# EEG-Electrodes.net
KiCad netlist of a schematic drawn in Altium Designer
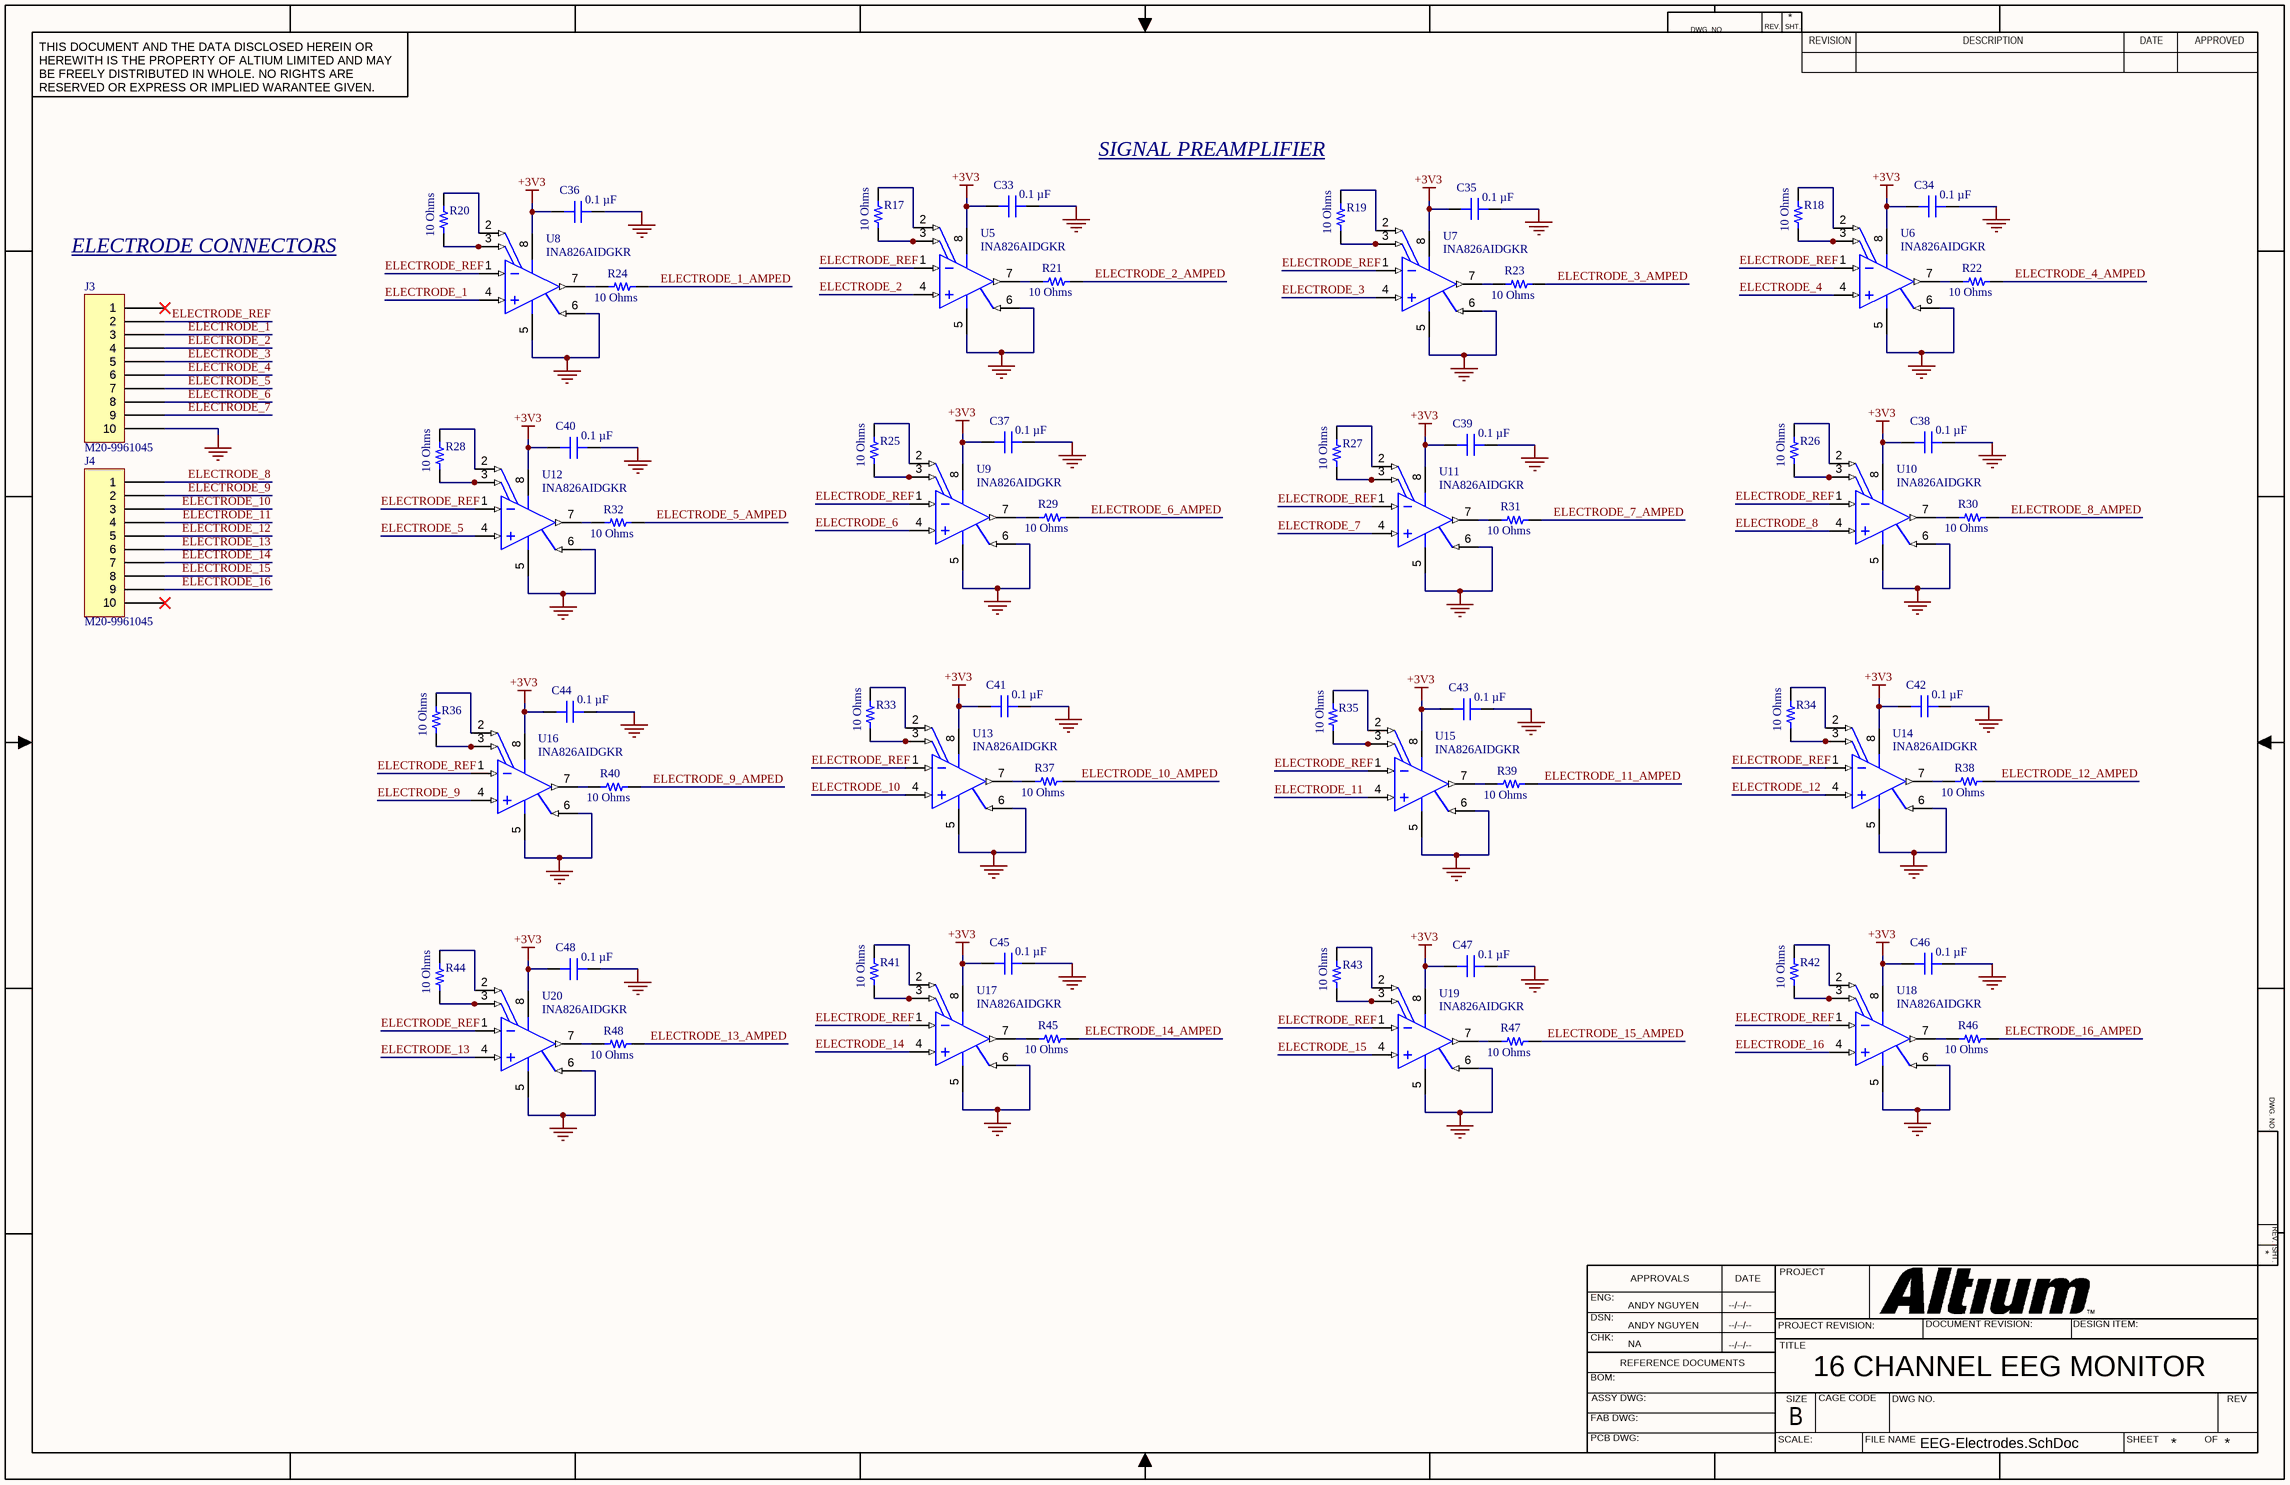
[diagram p0: EEG-Electrodes.SchDoc]

(export (version "E")
  (design (tool "Eeschema 10.0.6"))
  (components
    (comp (ref "C33")
      (value "0.1 µF")
      (footprint "CAP 0402_1005")
      (description "CAP CER 0402 0.1UF 16V X7R 10%")
      (fields (field (name "PART NUMBER") "C0402C104K4RECAUTO") (field (name "MANUFACTURER") "KEMET"))
      (libsource (lib "Celestial Altium Library - altium_library") (part "Capacitor"))
    )
    (comp (ref "C34")
      (value "0.1 µF")
      (footprint "CAP 0402_1005")
      (description "CAP CER 0402 0.1UF 16V X7R 10%")
      (fields (field (name "PART NUMBER") "C0402C104K4RECAUTO") (field (name "MANUFACTURER") "KEMET"))
      (libsource (lib "Celestial Altium Library - altium_library") (part "Capacitor"))
    )
    (comp (ref "C35")
      (value "0.1 µF")
      (footprint "CAP 0402_1005")
      (description "CAP CER 0402 0.1UF 16V X7R 10%")
      (fields (field (name "PART NUMBER") "C0402C104K4RECAUTO") (field (name "MANUFACTURER") "KEMET"))
      (libsource (lib "Celestial Altium Library - altium_library") (part "Capacitor"))
    )
    (comp (ref "C36")
      (value "0.1 µF")
      (footprint "CAP 0402_1005")
      (description "CAP CER 0402 0.1UF 16V X7R 10%")
      (fields (field (name "PART NUMBER") "C0402C104K4RECAUTO") (field (name "MANUFACTURER") "KEMET"))
      (libsource (lib "Celestial Altium Library - altium_library") (part "Capacitor"))
    )
    (comp (ref "C37")
      (value "0.1 µF")
      (footprint "CAP 0402_1005")
      (description "CAP CER 0402 0.1UF 16V X7R 10%")
      (fields (field (name "PART NUMBER") "C0402C104K4RECAUTO") (field (name "MANUFACTURER") "KEMET"))
      (libsource (lib "Celestial Altium Library - altium_library") (part "Capacitor"))
    )
    (comp (ref "C38")
      (value "0.1 µF")
      (footprint "CAP 0402_1005")
      (description "CAP CER 0402 0.1UF 16V X7R 10%")
      (fields (field (name "PART NUMBER") "C0402C104K4RECAUTO") (field (name "MANUFACTURER") "KEMET"))
      (libsource (lib "Celestial Altium Library - altium_library") (part "Capacitor"))
    )
    (comp (ref "C39")
      (value "0.1 µF")
      (footprint "CAP 0402_1005")
      (description "CAP CER 0402 0.1UF 16V X7R 10%")
      (fields (field (name "PART NUMBER") "C0402C104K4RECAUTO") (field (name "MANUFACTURER") "KEMET"))
      (libsource (lib "Celestial Altium Library - altium_library") (part "Capacitor"))
    )
    (comp (ref "C40")
      (value "0.1 µF")
      (footprint "CAP 0402_1005")
      (description "CAP CER 0402 0.1UF 16V X7R 10%")
      (fields (field (name "PART NUMBER") "C0402C104K4RECAUTO") (field (name "MANUFACTURER") "KEMET"))
      (libsource (lib "Celestial Altium Library - altium_library") (part "Capacitor"))
    )
    (comp (ref "C41")
      (value "0.1 µF")
      (footprint "CAP 0402_1005")
      (description "CAP CER 0402 0.1UF 16V X7R 10%")
      (fields (field (name "PART NUMBER") "C0402C104K4RECAUTO") (field (name "MANUFACTURER") "KEMET"))
      (libsource (lib "Celestial Altium Library - altium_library") (part "Capacitor"))
    )
    (comp (ref "C42")
      (value "0.1 µF")
      (footprint "CAP 0402_1005")
      (description "CAP CER 0402 0.1UF 16V X7R 10%")
      (fields (field (name "PART NUMBER") "C0402C104K4RECAUTO") (field (name "MANUFACTURER") "KEMET"))
      (libsource (lib "Celestial Altium Library - altium_library") (part "Capacitor"))
    )
    (comp (ref "C43")
      (value "0.1 µF")
      (footprint "CAP 0402_1005")
      (description "CAP CER 0402 0.1UF 16V X7R 10%")
      (fields (field (name "PART NUMBER") "C0402C104K4RECAUTO") (field (name "MANUFACTURER") "KEMET"))
      (libsource (lib "Celestial Altium Library - altium_library") (part "Capacitor"))
    )
    (comp (ref "C44")
      (value "0.1 µF")
      (footprint "CAP 0402_1005")
      (description "CAP CER 0402 0.1UF 16V X7R 10%")
      (fields (field (name "PART NUMBER") "C0402C104K4RECAUTO") (field (name "MANUFACTURER") "KEMET"))
      (libsource (lib "Celestial Altium Library - altium_library") (part "Capacitor"))
    )
    (comp (ref "C45")
      (value "0.1 µF")
      (footprint "CAP 0402_1005")
      (description "CAP CER 0402 0.1UF 16V X7R 10%")
      (fields (field (name "PART NUMBER") "C0402C104K4RECAUTO") (field (name "MANUFACTURER") "KEMET"))
      (libsource (lib "Celestial Altium Library - altium_library") (part "Capacitor"))
    )
    (comp (ref "C46")
      (value "0.1 µF")
      (footprint "CAP 0402_1005")
      (description "CAP CER 0402 0.1UF 16V X7R 10%")
      (fields (field (name "PART NUMBER") "C0402C104K4RECAUTO") (field (name "MANUFACTURER") "KEMET"))
      (libsource (lib "Celestial Altium Library - altium_library") (part "Capacitor"))
    )
    (comp (ref "C47")
      (value "0.1 µF")
      (footprint "CAP 0402_1005")
      (description "CAP CER 0402 0.1UF 16V X7R 10%")
      (fields (field (name "PART NUMBER") "C0402C104K4RECAUTO") (field (name "MANUFACTURER") "KEMET"))
      (libsource (lib "Celestial Altium Library - altium_library") (part "Capacitor"))
    )
    (comp (ref "C48")
      (value "0.1 µF")
      (footprint "CAP 0402_1005")
      (description "CAP CER 0402 0.1UF 16V X7R 10%")
      (fields (field (name "PART NUMBER") "C0402C104K4RECAUTO") (field (name "MANUFACTURER") "KEMET"))
      (libsource (lib "Celestial Altium Library - altium_library") (part "Capacitor"))
    )
    (comp (ref "J3")
      (value "M20-9961045")
      (footprint "HARWIN M20-9961045")
      (description "CONN HEADER R/A 10POS 2.54MM")
      (fields (field (name "MANUFACTURER") "Harwin Inc."))
      (libsource (lib "Celestial Altium Library - altium_library") (part "10 Pin"))
    )
    (comp (ref "J4")
      (value "M20-9961045")
      (footprint "HARWIN M20-9961045")
      (description "CONN HEADER R/A 10POS 2.54MM")
      (fields (field (name "MANUFACTURER") "Harwin Inc."))
      (libsource (lib "Celestial Altium Library - altium_library") (part "10 Pin"))
    )
    (comp (ref "R17")
      (value "10 Ohms")
      (footprint "RES 0402_1005")
      (description "RES SMD 10 OHM 0.5% 1/16W 0402")
      (fields
        (field (name "PART NUMBER") "ERA-2AKD100X")
        (field (name "MANUFACTURER") "Panasonic Electronic Components")
      )
      (libsource (lib "Celestial Altium Library - altium_library") (part "Resistor"))
    )
    (comp (ref "R18")
      (value "10 Ohms")
      (footprint "RES 0402_1005")
      (description "RES SMD 10 OHM 0.5% 1/16W 0402")
      (fields
        (field (name "PART NUMBER") "ERA-2AKD100X")
        (field (name "MANUFACTURER") "Panasonic Electronic Components")
      )
      (libsource (lib "Celestial Altium Library - altium_library") (part "Resistor"))
    )
    (comp (ref "R19")
      (value "10 Ohms")
      (footprint "RES 0402_1005")
      (description "RES SMD 10 OHM 0.5% 1/16W 0402")
      (fields
        (field (name "PART NUMBER") "ERA-2AKD100X")
        (field (name "MANUFACTURER") "Panasonic Electronic Components")
      )
      (libsource (lib "Celestial Altium Library - altium_library") (part "Resistor"))
    )
    (comp (ref "R20")
      (value "10 Ohms")
      (footprint "RES 0402_1005")
      (description "RES SMD 10 OHM 0.5% 1/16W 0402")
      (fields
        (field (name "PART NUMBER") "ERA-2AKD100X")
        (field (name "MANUFACTURER") "Panasonic Electronic Components")
      )
      (libsource (lib "Celestial Altium Library - altium_library") (part "Resistor"))
    )
    (comp (ref "R21")
      (value "10 Ohms")
      (footprint "RES 0402_1005")
      (description "RES SMD 10 OHM 0.5% 1/16W 0402")
      (fields
        (field (name "PART NUMBER") "ERA-2AKD100X")
        (field (name "MANUFACTURER") "Panasonic Electronic Components")
      )
      (libsource (lib "Celestial Altium Library - altium_library") (part "Resistor"))
    )
    (comp (ref "R22")
      (value "10 Ohms")
      (footprint "RES 0402_1005")
      (description "RES SMD 10 OHM 0.5% 1/16W 0402")
      (fields
        (field (name "PART NUMBER") "ERA-2AKD100X")
        (field (name "MANUFACTURER") "Panasonic Electronic Components")
      )
      (libsource (lib "Celestial Altium Library - altium_library") (part "Resistor"))
    )
    (comp (ref "R23")
      (value "10 Ohms")
      (footprint "RES 0402_1005")
      (description "RES SMD 10 OHM 0.5% 1/16W 0402")
      (fields
        (field (name "PART NUMBER") "ERA-2AKD100X")
        (field (name "MANUFACTURER") "Panasonic Electronic Components")
      )
      (libsource (lib "Celestial Altium Library - altium_library") (part "Resistor"))
    )
    (comp (ref "R24")
      (value "10 Ohms")
      (footprint "RES 0402_1005")
      (description "RES SMD 10 OHM 0.5% 1/16W 0402")
      (fields
        (field (name "PART NUMBER") "ERA-2AKD100X")
        (field (name "MANUFACTURER") "Panasonic Electronic Components")
      )
      (libsource (lib "Celestial Altium Library - altium_library") (part "Resistor"))
    )
    (comp (ref "R25")
      (value "10 Ohms")
      (footprint "RES 0402_1005")
      (description "RES SMD 10 OHM 0.5% 1/16W 0402")
      (fields
        (field (name "PART NUMBER") "ERA-2AKD100X")
        (field (name "MANUFACTURER") "Panasonic Electronic Components")
      )
      (libsource (lib "Celestial Altium Library - altium_library") (part "Resistor"))
    )
    (comp (ref "R26")
      (value "10 Ohms")
      (footprint "RES 0402_1005")
      (description "RES SMD 10 OHM 0.5% 1/16W 0402")
      (fields
        (field (name "PART NUMBER") "ERA-2AKD100X")
        (field (name "MANUFACTURER") "Panasonic Electronic Components")
      )
      (libsource (lib "Celestial Altium Library - altium_library") (part "Resistor"))
    )
    (comp (ref "R27")
      (value "10 Ohms")
      (footprint "RES 0402_1005")
      (description "RES SMD 10 OHM 0.5% 1/16W 0402")
      (fields
        (field (name "PART NUMBER") "ERA-2AKD100X")
        (field (name "MANUFACTURER") "Panasonic Electronic Components")
      )
      (libsource (lib "Celestial Altium Library - altium_library") (part "Resistor"))
    )
    (comp (ref "R28")
      (value "10 Ohms")
      (footprint "RES 0402_1005")
      (description "RES SMD 10 OHM 0.5% 1/16W 0402")
      (fields
        (field (name "PART NUMBER") "ERA-2AKD100X")
        (field (name "MANUFACTURER") "Panasonic Electronic Components")
      )
      (libsource (lib "Celestial Altium Library - altium_library") (part "Resistor"))
    )
    (comp (ref "R29")
      (value "10 Ohms")
      (footprint "RES 0402_1005")
      (description "RES SMD 10 OHM 0.5% 1/16W 0402")
      (fields
        (field (name "PART NUMBER") "ERA-2AKD100X")
        (field (name "MANUFACTURER") "Panasonic Electronic Components")
      )
      (libsource (lib "Celestial Altium Library - altium_library") (part "Resistor"))
    )
    (comp (ref "R30")
      (value "10 Ohms")
      (footprint "RES 0402_1005")
      (description "RES SMD 10 OHM 0.5% 1/16W 0402")
      (fields
        (field (name "PART NUMBER") "ERA-2AKD100X")
        (field (name "MANUFACTURER") "Panasonic Electronic Components")
      )
      (libsource (lib "Celestial Altium Library - altium_library") (part "Resistor"))
    )
    (comp (ref "R31")
      (value "10 Ohms")
      (footprint "RES 0402_1005")
      (description "RES SMD 10 OHM 0.5% 1/16W 0402")
      (fields
        (field (name "PART NUMBER") "ERA-2AKD100X")
        (field (name "MANUFACTURER") "Panasonic Electronic Components")
      )
      (libsource (lib "Celestial Altium Library - altium_library") (part "Resistor"))
    )
    (comp (ref "R32")
      (value "10 Ohms")
      (footprint "RES 0402_1005")
      (description "RES SMD 10 OHM 0.5% 1/16W 0402")
      (fields
        (field (name "PART NUMBER") "ERA-2AKD100X")
        (field (name "MANUFACTURER") "Panasonic Electronic Components")
      )
      (libsource (lib "Celestial Altium Library - altium_library") (part "Resistor"))
    )
    (comp (ref "R33")
      (value "10 Ohms")
      (footprint "RES 0402_1005")
      (description "RES SMD 10 OHM 0.5% 1/16W 0402")
      (fields
        (field (name "PART NUMBER") "ERA-2AKD100X")
        (field (name "MANUFACTURER") "Panasonic Electronic Components")
      )
      (libsource (lib "Celestial Altium Library - altium_library") (part "Resistor"))
    )
    (comp (ref "R34")
      (value "10 Ohms")
      (footprint "RES 0402_1005")
      (description "RES SMD 10 OHM 0.5% 1/16W 0402")
      (fields
        (field (name "PART NUMBER") "ERA-2AKD100X")
        (field (name "MANUFACTURER") "Panasonic Electronic Components")
      )
      (libsource (lib "Celestial Altium Library - altium_library") (part "Resistor"))
    )
    (comp (ref "R35")
      (value "10 Ohms")
      (footprint "RES 0402_1005")
      (description "RES SMD 10 OHM 0.5% 1/16W 0402")
      (fields
        (field (name "PART NUMBER") "ERA-2AKD100X")
        (field (name "MANUFACTURER") "Panasonic Electronic Components")
      )
      (libsource (lib "Celestial Altium Library - altium_library") (part "Resistor"))
    )
    (comp (ref "R36")
      (value "10 Ohms")
      (footprint "RES 0402_1005")
      (description "RES SMD 10 OHM 0.5% 1/16W 0402")
      (fields
        (field (name "PART NUMBER") "ERA-2AKD100X")
        (field (name "MANUFACTURER") "Panasonic Electronic Components")
      )
      (libsource (lib "Celestial Altium Library - altium_library") (part "Resistor"))
    )
    (comp (ref "R37")
      (value "10 Ohms")
      (footprint "RES 0402_1005")
      (description "RES SMD 10 OHM 0.5% 1/16W 0402")
      (fields
        (field (name "PART NUMBER") "ERA-2AKD100X")
        (field (name "MANUFACTURER") "Panasonic Electronic Components")
      )
      (libsource (lib "Celestial Altium Library - altium_library") (part "Resistor"))
    )
    (comp (ref "R38")
      (value "10 Ohms")
      (footprint "RES 0402_1005")
      (description "RES SMD 10 OHM 0.5% 1/16W 0402")
      (fields
        (field (name "PART NUMBER") "ERA-2AKD100X")
        (field (name "MANUFACTURER") "Panasonic Electronic Components")
      )
      (libsource (lib "Celestial Altium Library - altium_library") (part "Resistor"))
    )
    (comp (ref "R39")
      (value "10 Ohms")
      (footprint "RES 0402_1005")
      (description "RES SMD 10 OHM 0.5% 1/16W 0402")
      (fields
        (field (name "PART NUMBER") "ERA-2AKD100X")
        (field (name "MANUFACTURER") "Panasonic Electronic Components")
      )
      (libsource (lib "Celestial Altium Library - altium_library") (part "Resistor"))
    )
    (comp (ref "R40")
      (value "10 Ohms")
      (footprint "RES 0402_1005")
      (description "RES SMD 10 OHM 0.5% 1/16W 0402")
      (fields
        (field (name "PART NUMBER") "ERA-2AKD100X")
        (field (name "MANUFACTURER") "Panasonic Electronic Components")
      )
      (libsource (lib "Celestial Altium Library - altium_library") (part "Resistor"))
    )
    (comp (ref "R41")
      (value "10 Ohms")
      (footprint "RES 0402_1005")
      (description "RES SMD 10 OHM 0.5% 1/16W 0402")
      (fields
        (field (name "PART NUMBER") "ERA-2AKD100X")
        (field (name "MANUFACTURER") "Panasonic Electronic Components")
      )
      (libsource (lib "Celestial Altium Library - altium_library") (part "Resistor"))
    )
    (comp (ref "R42")
      (value "10 Ohms")
      (footprint "RES 0402_1005")
      (description "RES SMD 10 OHM 0.5% 1/16W 0402")
      (fields
        (field (name "PART NUMBER") "ERA-2AKD100X")
        (field (name "MANUFACTURER") "Panasonic Electronic Components")
      )
      (libsource (lib "Celestial Altium Library - altium_library") (part "Resistor"))
    )
    (comp (ref "R43")
      (value "10 Ohms")
      (footprint "RES 0402_1005")
      (description "RES SMD 10 OHM 0.5% 1/16W 0402")
      (fields
        (field (name "PART NUMBER") "ERA-2AKD100X")
        (field (name "MANUFACTURER") "Panasonic Electronic Components")
      )
      (libsource (lib "Celestial Altium Library - altium_library") (part "Resistor"))
    )
    (comp (ref "R44")
      (value "10 Ohms")
      (footprint "RES 0402_1005")
      (description "RES SMD 10 OHM 0.5% 1/16W 0402")
      (fields
        (field (name "PART NUMBER") "ERA-2AKD100X")
        (field (name "MANUFACTURER") "Panasonic Electronic Components")
      )
      (libsource (lib "Celestial Altium Library - altium_library") (part "Resistor"))
    )
    (comp (ref "R45")
      (value "10 Ohms")
      (footprint "RES 0402_1005")
      (description "RES SMD 10 OHM 0.5% 1/16W 0402")
      (fields
        (field (name "PART NUMBER") "ERA-2AKD100X")
        (field (name "MANUFACTURER") "Panasonic Electronic Components")
      )
      (libsource (lib "Celestial Altium Library - altium_library") (part "Resistor"))
    )
    (comp (ref "R46")
      (value "10 Ohms")
      (footprint "RES 0402_1005")
      (description "RES SMD 10 OHM 0.5% 1/16W 0402")
      (fields
        (field (name "PART NUMBER") "ERA-2AKD100X")
        (field (name "MANUFACTURER") "Panasonic Electronic Components")
      )
      (libsource (lib "Celestial Altium Library - altium_library") (part "Resistor"))
    )
    (comp (ref "R47")
      (value "10 Ohms")
      (footprint "RES 0402_1005")
      (description "RES SMD 10 OHM 0.5% 1/16W 0402")
      (fields
        (field (name "PART NUMBER") "ERA-2AKD100X")
        (field (name "MANUFACTURER") "Panasonic Electronic Components")
      )
      (libsource (lib "Celestial Altium Library - altium_library") (part "Resistor"))
    )
    (comp (ref "R48")
      (value "10 Ohms")
      (footprint "RES 0402_1005")
      (description "RES SMD 10 OHM 0.5% 1/16W 0402")
      (fields
        (field (name "PART NUMBER") "ERA-2AKD100X")
        (field (name "MANUFACTURER") "Panasonic Electronic Components")
      )
      (libsource (lib "Celestial Altium Library - altium_library") (part "Resistor"))
    )
    (comp (ref "U5")
      (value "INA826AIDGKR")
      (footprint "DGK0008A_N")
      (fields (field (name "MANUFACTURER") "Texas Instruments"))
      (libsource (lib "Altium Content Vault") (part "TI-INA826X8"))
    )
    (comp (ref "U6")
      (value "INA826AIDGKR")
      (footprint "DGK0008A_N")
      (fields (field (name "MANUFACTURER") "Texas Instruments"))
      (libsource (lib "Altium Content Vault") (part "TI-INA826X8"))
    )
    (comp (ref "U7")
      (value "INA826AIDGKR")
      (footprint "DGK0008A_N")
      (fields (field (name "MANUFACTURER") "Texas Instruments"))
      (libsource (lib "Altium Content Vault") (part "TI-INA826X8"))
    )
    (comp (ref "U8")
      (value "INA826AIDGKR")
      (footprint "DGK0008A_N")
      (fields (field (name "MANUFACTURER") "Texas Instruments"))
      (libsource (lib "Altium Content Vault") (part "TI-INA826X8"))
    )
    (comp (ref "U9")
      (value "INA826AIDGKR")
      (footprint "DGK0008A_N")
      (fields (field (name "MANUFACTURER") "Texas Instruments"))
      (libsource (lib "Altium Content Vault") (part "TI-INA826X8"))
    )
    (comp (ref "U10")
      (value "INA826AIDGKR")
      (footprint "DGK0008A_N")
      (fields (field (name "MANUFACTURER") "Texas Instruments"))
      (libsource (lib "Altium Content Vault") (part "TI-INA826X8"))
    )
    (comp (ref "U11")
      (value "INA826AIDGKR")
      (footprint "DGK0008A_N")
      (fields (field (name "MANUFACTURER") "Texas Instruments"))
      (libsource (lib "Altium Content Vault") (part "TI-INA826X8"))
    )
    (comp (ref "U12")
      (value "INA826AIDGKR")
      (footprint "DGK0008A_N")
      (fields (field (name "MANUFACTURER") "Texas Instruments"))
      (libsource (lib "Altium Content Vault") (part "TI-INA826X8"))
    )
    (comp (ref "U13")
      (value "INA826AIDGKR")
      (footprint "DGK0008A_N")
      (fields (field (name "MANUFACTURER") "Texas Instruments"))
      (libsource (lib "Altium Content Vault") (part "TI-INA826X8"))
    )
    (comp (ref "U14")
      (value "INA826AIDGKR")
      (footprint "DGK0008A_N")
      (fields (field (name "MANUFACTURER") "Texas Instruments"))
      (libsource (lib "Altium Content Vault") (part "TI-INA826X8"))
    )
    (comp (ref "U15")
      (value "INA826AIDGKR")
      (footprint "DGK0008A_N")
      (fields (field (name "MANUFACTURER") "Texas Instruments"))
      (libsource (lib "Altium Content Vault") (part "TI-INA826X8"))
    )
    (comp (ref "U16")
      (value "INA826AIDGKR")
      (footprint "DGK0008A_N")
      (fields (field (name "MANUFACTURER") "Texas Instruments"))
      (libsource (lib "Altium Content Vault") (part "TI-INA826X8"))
    )
    (comp (ref "U17")
      (value "INA826AIDGKR")
      (footprint "DGK0008A_N")
      (fields (field (name "MANUFACTURER") "Texas Instruments"))
      (libsource (lib "Altium Content Vault") (part "TI-INA826X8"))
    )
    (comp (ref "U18")
      (value "INA826AIDGKR")
      (footprint "DGK0008A_N")
      (fields (field (name "MANUFACTURER") "Texas Instruments"))
      (libsource (lib "Altium Content Vault") (part "TI-INA826X8"))
    )
    (comp (ref "U19")
      (value "INA826AIDGKR")
      (footprint "DGK0008A_N")
      (fields (field (name "MANUFACTURER") "Texas Instruments"))
      (libsource (lib "Altium Content Vault") (part "TI-INA826X8"))
    )
    (comp (ref "U20")
      (value "INA826AIDGKR")
      (footprint "DGK0008A_N")
      (fields (field (name "MANUFACTURER") "Texas Instruments"))
      (libsource (lib "Altium Content Vault") (part "TI-INA826X8"))
    )
  )
  (nets
    (net (code "1") (name "+3V3") (class "Default")
      (node (ref "C33") (pin "2") (pinfunction "2_2") (pintype "passive"))
      (node (ref "C34") (pin "2") (pinfunction "2_2") (pintype "passive"))
      (node (ref "C35") (pin "2") (pinfunction "2_2") (pintype "passive"))
      (node (ref "C36") (pin "2") (pinfunction "2_2") (pintype "passive"))
      (node (ref "C37") (pin "2") (pinfunction "2_2") (pintype "passive"))
      (node (ref "C38") (pin "2") (pinfunction "2_2") (pintype "passive"))
      (node (ref "C39") (pin "2") (pinfunction "2_2") (pintype "passive"))
      (node (ref "C40") (pin "2") (pinfunction "2_2") (pintype "passive"))
      (node (ref "C41") (pin "2") (pinfunction "2_2") (pintype "passive"))
      (node (ref "C42") (pin "2") (pinfunction "2_2") (pintype "passive"))
      (node (ref "C43") (pin "2") (pinfunction "2_2") (pintype "passive"))
      (node (ref "C44") (pin "2") (pinfunction "2_2") (pintype "passive"))
      (node (ref "C45") (pin "2") (pinfunction "2_2") (pintype "passive"))
      (node (ref "C46") (pin "2") (pinfunction "2_2") (pintype "passive"))
      (node (ref "C47") (pin "2") (pinfunction "2_2") (pintype "passive"))
      (node (ref "C48") (pin "2") (pinfunction "2_2") (pintype "passive"))
      (node (ref "U10") (pin "8") (pinfunction "VS+_8") (pintype "power_in"))
      (node (ref "U11") (pin "8") (pinfunction "VS+_8") (pintype "power_in"))
      (node (ref "U12") (pin "8") (pinfunction "VS+_8") (pintype "power_in"))
      (node (ref "U13") (pin "8") (pinfunction "VS+_8") (pintype "power_in"))
      (node (ref "U14") (pin "8") (pinfunction "VS+_8") (pintype "power_in"))
      (node (ref "U15") (pin "8") (pinfunction "VS+_8") (pintype "power_in"))
      (node (ref "U16") (pin "8") (pinfunction "VS+_8") (pintype "power_in"))
      (node (ref "U17") (pin "8") (pinfunction "VS+_8") (pintype "power_in"))
      (node (ref "U18") (pin "8") (pinfunction "VS+_8") (pintype "power_in"))
      (node (ref "U19") (pin "8") (pinfunction "VS+_8") (pintype "power_in"))
      (node (ref "U20") (pin "8") (pinfunction "VS+_8") (pintype "power_in"))
      (node (ref "U5") (pin "8") (pinfunction "VS+_8") (pintype "power_in"))
      (node (ref "U6") (pin "8") (pinfunction "VS+_8") (pintype "power_in"))
      (node (ref "U7") (pin "8") (pinfunction "VS+_8") (pintype "power_in"))
      (node (ref "U8") (pin "8") (pinfunction "VS+_8") (pintype "power_in"))
      (node (ref "U9") (pin "8") (pinfunction "VS+_8") (pintype "power_in"))
    )
    (net (code "2") (name "/ELECTRODE_1") (class "Default")
      (node (ref "J3") (pin "3") (pinfunction "3_3") (pintype "passive"))
      (node (ref "U8") (pin "4") (pinfunction "IN+_4") (pintype "input"))
    )
    (net (code "3") (name "/ELECTRODE_1_AMPED") (class "Default")
      (node (ref "R24") (pin "2") (pinfunction "2_2") (pintype "passive"))
    )
    (net (code "4") (name "/ELECTRODE_2") (class "Default")
      (node (ref "J3") (pin "4") (pinfunction "4_4") (pintype "passive"))
      (node (ref "U5") (pin "4") (pinfunction "IN+_4") (pintype "input"))
    )
    (net (code "5") (name "/ELECTRODE_2_AMPED") (class "Default")
      (node (ref "R21") (pin "2") (pinfunction "2_2") (pintype "passive"))
    )
    (net (code "6") (name "/ELECTRODE_3") (class "Default")
      (node (ref "J3") (pin "5") (pinfunction "5_5") (pintype "passive"))
      (node (ref "U7") (pin "4") (pinfunction "IN+_4") (pintype "input"))
    )
    (net (code "7") (name "/ELECTRODE_3_AMPED") (class "Default")
      (node (ref "R23") (pin "2") (pinfunction "2_2") (pintype "passive"))
    )
    (net (code "8") (name "/ELECTRODE_4") (class "Default")
      (node (ref "J3") (pin "6") (pinfunction "6_6") (pintype "passive"))
      (node (ref "U6") (pin "4") (pinfunction "IN+_4") (pintype "input"))
    )
    (net (code "9") (name "/ELECTRODE_4_AMPED") (class "Default")
      (node (ref "R22") (pin "2") (pinfunction "2_2") (pintype "passive"))
    )
    (net (code "10") (name "/ELECTRODE_5") (class "Default")
      (node (ref "J3") (pin "7") (pinfunction "7_7") (pintype "passive"))
      (node (ref "U12") (pin "4") (pinfunction "IN+_4") (pintype "input"))
    )
    (net (code "11") (name "/ELECTRODE_5_AMPED") (class "Default")
      (node (ref "R32") (pin "2") (pinfunction "2_2") (pintype "passive"))
    )
    (net (code "12") (name "/ELECTRODE_6") (class "Default")
      (node (ref "J3") (pin "8") (pinfunction "8_8") (pintype "passive"))
      (node (ref "U9") (pin "4") (pinfunction "IN+_4") (pintype "input"))
    )
    (net (code "13") (name "/ELECTRODE_6_AMPED") (class "Default")
      (node (ref "R29") (pin "2") (pinfunction "2_2") (pintype "passive"))
    )
    (net (code "14") (name "/ELECTRODE_7") (class "Default")
      (node (ref "J3") (pin "9") (pinfunction "9_9") (pintype "passive"))
      (node (ref "U11") (pin "4") (pinfunction "IN+_4") (pintype "input"))
    )
    (net (code "15") (name "/ELECTRODE_7_AMPED") (class "Default")
      (node (ref "R31") (pin "2") (pinfunction "2_2") (pintype "passive"))
    )
    (net (code "16") (name "/ELECTRODE_8") (class "Default")
      (node (ref "J4") (pin "1") (pinfunction "1_1") (pintype "passive"))
      (node (ref "U10") (pin "4") (pinfunction "IN+_4") (pintype "input"))
    )
    (net (code "17") (name "/ELECTRODE_8_AMPED") (class "Default")
      (node (ref "R30") (pin "2") (pinfunction "2_2") (pintype "passive"))
    )
    (net (code "18") (name "/ELECTRODE_9") (class "Default")
      (node (ref "J4") (pin "2") (pinfunction "2_2") (pintype "passive"))
      (node (ref "U16") (pin "4") (pinfunction "IN+_4") (pintype "input"))
    )
    (net (code "19") (name "/ELECTRODE_9_AMPED") (class "Default")
      (node (ref "R40") (pin "2") (pinfunction "2_2") (pintype "passive"))
    )
    (net (code "20") (name "/ELECTRODE_10") (class "Default")
      (node (ref "J4") (pin "3") (pinfunction "3_3") (pintype "passive"))
      (node (ref "U13") (pin "4") (pinfunction "IN+_4") (pintype "input"))
    )
    (net (code "21") (name "/ELECTRODE_10_AMPED") (class "Default")
      (node (ref "R37") (pin "2") (pinfunction "2_2") (pintype "passive"))
    )
    (net (code "22") (name "/ELECTRODE_11") (class "Default")
      (node (ref "J4") (pin "4") (pinfunction "4_4") (pintype "passive"))
      (node (ref "U15") (pin "4") (pinfunction "IN+_4") (pintype "input"))
    )
    (net (code "23") (name "/ELECTRODE_11_AMPED") (class "Default")
      (node (ref "R39") (pin "2") (pinfunction "2_2") (pintype "passive"))
    )
    (net (code "24") (name "/ELECTRODE_12") (class "Default")
      (node (ref "J4") (pin "5") (pinfunction "5_5") (pintype "passive"))
      (node (ref "U14") (pin "4") (pinfunction "IN+_4") (pintype "input"))
    )
    (net (code "25") (name "/ELECTRODE_12_AMPED") (class "Default")
      (node (ref "R38") (pin "2") (pinfunction "2_2") (pintype "passive"))
    )
    (net (code "26") (name "/ELECTRODE_13") (class "Default")
      (node (ref "J4") (pin "6") (pinfunction "6_6") (pintype "passive"))
      (node (ref "U20") (pin "4") (pinfunction "IN+_4") (pintype "input"))
    )
    (net (code "27") (name "/ELECTRODE_13_AMPED") (class "Default")
      (node (ref "R48") (pin "2") (pinfunction "2_2") (pintype "passive"))
    )
    (net (code "28") (name "/ELECTRODE_14") (class "Default")
      (node (ref "J4") (pin "7") (pinfunction "7_7") (pintype "passive"))
      (node (ref "U17") (pin "4") (pinfunction "IN+_4") (pintype "input"))
    )
    (net (code "29") (name "/ELECTRODE_14_AMPED") (class "Default")
      (node (ref "R45") (pin "2") (pinfunction "2_2") (pintype "passive"))
    )
    (net (code "30") (name "/ELECTRODE_15") (class "Default")
      (node (ref "J4") (pin "8") (pinfunction "8_8") (pintype "passive"))
      (node (ref "U19") (pin "4") (pinfunction "IN+_4") (pintype "input"))
    )
    (net (code "31") (name "/ELECTRODE_15_AMPED") (class "Default")
      (node (ref "R47") (pin "2") (pinfunction "2_2") (pintype "passive"))
    )
    (net (code "32") (name "/ELECTRODE_16") (class "Default")
      (node (ref "J4") (pin "9") (pinfunction "9_9") (pintype "passive"))
      (node (ref "U18") (pin "4") (pinfunction "IN+_4") (pintype "input"))
    )
    (net (code "33") (name "/ELECTRODE_16_AMPED") (class "Default")
      (node (ref "R46") (pin "2") (pinfunction "2_2") (pintype "passive"))
    )
    (net (code "34") (name "/ELECTRODE_REF") (class "Default")
      (node (ref "J3") (pin "2") (pinfunction "2_2") (pintype "passive"))
      (node (ref "U10") (pin "1") (pinfunction "IN-_1") (pintype "input"))
      (node (ref "U11") (pin "1") (pinfunction "IN-_1") (pintype "input"))
      (node (ref "U12") (pin "1") (pinfunction "IN-_1") (pintype "input"))
      (node (ref "U13") (pin "1") (pinfunction "IN-_1") (pintype "input"))
      (node (ref "U14") (pin "1") (pinfunction "IN-_1") (pintype "input"))
      (node (ref "U15") (pin "1") (pinfunction "IN-_1") (pintype "input"))
      (node (ref "U16") (pin "1") (pinfunction "IN-_1") (pintype "input"))
      (node (ref "U17") (pin "1") (pinfunction "IN-_1") (pintype "input"))
      (node (ref "U18") (pin "1") (pinfunction "IN-_1") (pintype "input"))
      (node (ref "U19") (pin "1") (pinfunction "IN-_1") (pintype "input"))
      (node (ref "U20") (pin "1") (pinfunction "IN-_1") (pintype "input"))
      (node (ref "U5") (pin "1") (pinfunction "IN-_1") (pintype "input"))
      (node (ref "U6") (pin "1") (pinfunction "IN-_1") (pintype "input"))
      (node (ref "U7") (pin "1") (pinfunction "IN-_1") (pintype "input"))
      (node (ref "U8") (pin "1") (pinfunction "IN-_1") (pintype "input"))
      (node (ref "U9") (pin "1") (pinfunction "IN-_1") (pintype "input"))
    )
    (net (code "35") (name "GND") (class "Default")
      (node (ref "C33") (pin "1") (pinfunction "1_1") (pintype "passive"))
      (node (ref "C34") (pin "1") (pinfunction "1_1") (pintype "passive"))
      (node (ref "C35") (pin "1") (pinfunction "1_1") (pintype "passive"))
      (node (ref "C36") (pin "1") (pinfunction "1_1") (pintype "passive"))
      (node (ref "C37") (pin "1") (pinfunction "1_1") (pintype "passive"))
      (node (ref "C38") (pin "1") (pinfunction "1_1") (pintype "passive"))
      (node (ref "C39") (pin "1") (pinfunction "1_1") (pintype "passive"))
      (node (ref "C40") (pin "1") (pinfunction "1_1") (pintype "passive"))
      (node (ref "C41") (pin "1") (pinfunction "1_1") (pintype "passive"))
      (node (ref "C42") (pin "1") (pinfunction "1_1") (pintype "passive"))
      (node (ref "C43") (pin "1") (pinfunction "1_1") (pintype "passive"))
      (node (ref "C44") (pin "1") (pinfunction "1_1") (pintype "passive"))
      (node (ref "C45") (pin "1") (pinfunction "1_1") (pintype "passive"))
      (node (ref "C46") (pin "1") (pinfunction "1_1") (pintype "passive"))
      (node (ref "C47") (pin "1") (pinfunction "1_1") (pintype "passive"))
      (node (ref "C48") (pin "1") (pinfunction "1_1") (pintype "passive"))
      (node (ref "J3") (pin "10") (pinfunction "10_10") (pintype "passive"))
      (node (ref "U10") (pin "5") (pinfunction "VS-_5") (pintype "power_in"))
      (node (ref "U10") (pin "6") (pinfunction "REF_6") (pintype "input"))
      (node (ref "U11") (pin "5") (pinfunction "VS-_5") (pintype "power_in"))
      (node (ref "U11") (pin "6") (pinfunction "REF_6") (pintype "input"))
      (node (ref "U12") (pin "5") (pinfunction "VS-_5") (pintype "power_in"))
      (node (ref "U12") (pin "6") (pinfunction "REF_6") (pintype "input"))
      (node (ref "U13") (pin "5") (pinfunction "VS-_5") (pintype "power_in"))
      (node (ref "U13") (pin "6") (pinfunction "REF_6") (pintype "input"))
      (node (ref "U14") (pin "5") (pinfunction "VS-_5") (pintype "power_in"))
      (node (ref "U14") (pin "6") (pinfunction "REF_6") (pintype "input"))
      (node (ref "U15") (pin "5") (pinfunction "VS-_5") (pintype "power_in"))
      (node (ref "U15") (pin "6") (pinfunction "REF_6") (pintype "input"))
      (node (ref "U16") (pin "5") (pinfunction "VS-_5") (pintype "power_in"))
      (node (ref "U16") (pin "6") (pinfunction "REF_6") (pintype "input"))
      (node (ref "U17") (pin "5") (pinfunction "VS-_5") (pintype "power_in"))
      (node (ref "U17") (pin "6") (pinfunction "REF_6") (pintype "input"))
      (node (ref "U18") (pin "5") (pinfunction "VS-_5") (pintype "power_in"))
      (node (ref "U18") (pin "6") (pinfunction "REF_6") (pintype "input"))
      (node (ref "U19") (pin "5") (pinfunction "VS-_5") (pintype "power_in"))
      (node (ref "U19") (pin "6") (pinfunction "REF_6") (pintype "input"))
      (node (ref "U20") (pin "5") (pinfunction "VS-_5") (pintype "power_in"))
      (node (ref "U20") (pin "6") (pinfunction "REF_6") (pintype "input"))
      (node (ref "U5") (pin "5") (pinfunction "VS-_5") (pintype "power_in"))
      (node (ref "U5") (pin "6") (pinfunction "REF_6") (pintype "input"))
      (node (ref "U6") (pin "5") (pinfunction "VS-_5") (pintype "power_in"))
      (node (ref "U6") (pin "6") (pinfunction "REF_6") (pintype "input"))
      (node (ref "U7") (pin "5") (pinfunction "VS-_5") (pintype "power_in"))
      (node (ref "U7") (pin "6") (pinfunction "REF_6") (pintype "input"))
      (node (ref "U8") (pin "5") (pinfunction "VS-_5") (pintype "power_in"))
      (node (ref "U8") (pin "6") (pinfunction "REF_6") (pintype "input"))
      (node (ref "U9") (pin "5") (pinfunction "VS-_5") (pintype "power_in"))
      (node (ref "U9") (pin "6") (pinfunction "REF_6") (pintype "input"))
    )
    (net (code "36") (name "Net-(R17-Pad1)") (class "Default")
      (node (ref "R17") (pin "1") (pinfunction "1_1") (pintype "passive"))
      (node (ref "U5") (pin "3") (pinfunction "RG_3") (pintype "input"))
    )
    (net (code "37") (name "Net-(R17-Pad2)") (class "Default")
      (node (ref "R17") (pin "2") (pinfunction "2_2") (pintype "passive"))
      (node (ref "U5") (pin "2") (pinfunction "RG_2") (pintype "input"))
    )
    (net (code "38") (name "Net-(R18-Pad1)") (class "Default")
      (node (ref "R18") (pin "1") (pinfunction "1_1") (pintype "passive"))
      (node (ref "U6") (pin "3") (pinfunction "RG_3") (pintype "input"))
    )
    (net (code "39") (name "Net-(R18-Pad2)") (class "Default")
      (node (ref "R18") (pin "2") (pinfunction "2_2") (pintype "passive"))
      (node (ref "U6") (pin "2") (pinfunction "RG_2") (pintype "input"))
    )
    (net (code "40") (name "Net-(R19-Pad1)") (class "Default")
      (node (ref "R19") (pin "1") (pinfunction "1_1") (pintype "passive"))
      (node (ref "U7") (pin "3") (pinfunction "RG_3") (pintype "input"))
    )
    (net (code "41") (name "Net-(R19-Pad2)") (class "Default")
      (node (ref "R19") (pin "2") (pinfunction "2_2") (pintype "passive"))
      (node (ref "U7") (pin "2") (pinfunction "RG_2") (pintype "input"))
    )
    (net (code "42") (name "Net-(R20-Pad1)") (class "Default")
      (node (ref "R20") (pin "1") (pinfunction "1_1") (pintype "passive"))
      (node (ref "U8") (pin "3") (pinfunction "RG_3") (pintype "input"))
    )
    (net (code "43") (name "Net-(R20-Pad2)") (class "Default")
      (node (ref "R20") (pin "2") (pinfunction "2_2") (pintype "passive"))
      (node (ref "U8") (pin "2") (pinfunction "RG_2") (pintype "input"))
    )
    (net (code "44") (name "Net-(R25-Pad1)") (class "Default")
      (node (ref "R25") (pin "1") (pinfunction "1_1") (pintype "passive"))
      (node (ref "U9") (pin "3") (pinfunction "RG_3") (pintype "input"))
    )
    (net (code "45") (name "Net-(R25-Pad2)") (class "Default")
      (node (ref "R25") (pin "2") (pinfunction "2_2") (pintype "passive"))
      (node (ref "U9") (pin "2") (pinfunction "RG_2") (pintype "input"))
    )
    (net (code "46") (name "Net-(R26-Pad1)") (class "Default")
      (node (ref "R26") (pin "1") (pinfunction "1_1") (pintype "passive"))
      (node (ref "U10") (pin "3") (pinfunction "RG_3") (pintype "input"))
    )
    (net (code "47") (name "Net-(R26-Pad2)") (class "Default")
      (node (ref "R26") (pin "2") (pinfunction "2_2") (pintype "passive"))
      (node (ref "U10") (pin "2") (pinfunction "RG_2") (pintype "input"))
    )
    (net (code "48") (name "Net-(R27-Pad1)") (class "Default")
      (node (ref "R27") (pin "1") (pinfunction "1_1") (pintype "passive"))
      (node (ref "U11") (pin "3") (pinfunction "RG_3") (pintype "input"))
    )
    (net (code "49") (name "Net-(R27-Pad2)") (class "Default")
      (node (ref "R27") (pin "2") (pinfunction "2_2") (pintype "passive"))
      (node (ref "U11") (pin "2") (pinfunction "RG_2") (pintype "input"))
    )
    (net (code "50") (name "Net-(R28-Pad1)") (class "Default")
      (node (ref "R28") (pin "1") (pinfunction "1_1") (pintype "passive"))
      (node (ref "U12") (pin "3") (pinfunction "RG_3") (pintype "input"))
    )
    (net (code "51") (name "Net-(R28-Pad2)") (class "Default")
      (node (ref "R28") (pin "2") (pinfunction "2_2") (pintype "passive"))
      (node (ref "U12") (pin "2") (pinfunction "RG_2") (pintype "input"))
    )
    (net (code "52") (name "Net-(R33-Pad1)") (class "Default")
      (node (ref "R33") (pin "1") (pinfunction "1_1") (pintype "passive"))
      (node (ref "U13") (pin "3") (pinfunction "RG_3") (pintype "input"))
    )
    (net (code "53") (name "Net-(R33-Pad2)") (class "Default")
      (node (ref "R33") (pin "2") (pinfunction "2_2") (pintype "passive"))
      (node (ref "U13") (pin "2") (pinfunction "RG_2") (pintype "input"))
    )
    (net (code "54") (name "Net-(R34-Pad1)") (class "Default")
      (node (ref "R34") (pin "1") (pinfunction "1_1") (pintype "passive"))
      (node (ref "U14") (pin "3") (pinfunction "RG_3") (pintype "input"))
    )
    (net (code "55") (name "Net-(R34-Pad2)") (class "Default")
      (node (ref "R34") (pin "2") (pinfunction "2_2") (pintype "passive"))
      (node (ref "U14") (pin "2") (pinfunction "RG_2") (pintype "input"))
    )
    (net (code "56") (name "Net-(R35-Pad1)") (class "Default")
      (node (ref "R35") (pin "1") (pinfunction "1_1") (pintype "passive"))
      (node (ref "U15") (pin "3") (pinfunction "RG_3") (pintype "input"))
    )
    (net (code "57") (name "Net-(R35-Pad2)") (class "Default")
      (node (ref "R35") (pin "2") (pinfunction "2_2") (pintype "passive"))
      (node (ref "U15") (pin "2") (pinfunction "RG_2") (pintype "input"))
    )
    (net (code "58") (name "Net-(R36-Pad1)") (class "Default")
      (node (ref "R36") (pin "1") (pinfunction "1_1") (pintype "passive"))
      (node (ref "U16") (pin "3") (pinfunction "RG_3") (pintype "input"))
    )
    (net (code "59") (name "Net-(R36-Pad2)") (class "Default")
      (node (ref "R36") (pin "2") (pinfunction "2_2") (pintype "passive"))
      (node (ref "U16") (pin "2") (pinfunction "RG_2") (pintype "input"))
    )
    (net (code "60") (name "Net-(R41-Pad1)") (class "Default")
      (node (ref "R41") (pin "1") (pinfunction "1_1") (pintype "passive"))
      (node (ref "U17") (pin "3") (pinfunction "RG_3") (pintype "input"))
    )
    (net (code "61") (name "Net-(R41-Pad2)") (class "Default")
      (node (ref "R41") (pin "2") (pinfunction "2_2") (pintype "passive"))
      (node (ref "U17") (pin "2") (pinfunction "RG_2") (pintype "input"))
    )
    (net (code "62") (name "Net-(R42-Pad1)") (class "Default")
      (node (ref "R42") (pin "1") (pinfunction "1_1") (pintype "passive"))
      (node (ref "U18") (pin "3") (pinfunction "RG_3") (pintype "input"))
    )
    (net (code "63") (name "Net-(R42-Pad2)") (class "Default")
      (node (ref "R42") (pin "2") (pinfunction "2_2") (pintype "passive"))
      (node (ref "U18") (pin "2") (pinfunction "RG_2") (pintype "input"))
    )
    (net (code "64") (name "Net-(R43-Pad1)") (class "Default")
      (node (ref "R43") (pin "1") (pinfunction "1_1") (pintype "passive"))
      (node (ref "U19") (pin "3") (pinfunction "RG_3") (pintype "input"))
    )
    (net (code "65") (name "Net-(R43-Pad2)") (class "Default")
      (node (ref "R43") (pin "2") (pinfunction "2_2") (pintype "passive"))
      (node (ref "U19") (pin "2") (pinfunction "RG_2") (pintype "input"))
    )
    (net (code "66") (name "Net-(R44-Pad1)") (class "Default")
      (node (ref "R44") (pin "1") (pinfunction "1_1") (pintype "passive"))
      (node (ref "U20") (pin "3") (pinfunction "RG_3") (pintype "input"))
    )
    (net (code "67") (name "Net-(R44-Pad2)") (class "Default")
      (node (ref "R44") (pin "2") (pinfunction "2_2") (pintype "passive"))
      (node (ref "U20") (pin "2") (pinfunction "RG_2") (pintype "input"))
    )
    (net (code "68") (name "Net-(U5-VOUT)") (class "Default")
      (node (ref "R21") (pin "1") (pinfunction "1_1") (pintype "passive"))
      (node (ref "U5") (pin "7") (pinfunction "VOUT_7") (pintype "output"))
    )
    (net (code "69") (name "Net-(U6-VOUT)") (class "Default")
      (node (ref "R22") (pin "1") (pinfunction "1_1") (pintype "passive"))
      (node (ref "U6") (pin "7") (pinfunction "VOUT_7") (pintype "output"))
    )
    (net (code "70") (name "Net-(U7-VOUT)") (class "Default")
      (node (ref "R23") (pin "1") (pinfunction "1_1") (pintype "passive"))
      (node (ref "U7") (pin "7") (pinfunction "VOUT_7") (pintype "output"))
    )
    (net (code "71") (name "Net-(U8-VOUT)") (class "Default")
      (node (ref "R24") (pin "1") (pinfunction "1_1") (pintype "passive"))
      (node (ref "U8") (pin "7") (pinfunction "VOUT_7") (pintype "output"))
    )
    (net (code "72") (name "Net-(U9-VOUT)") (class "Default")
      (node (ref "R29") (pin "1") (pinfunction "1_1") (pintype "passive"))
      (node (ref "U9") (pin "7") (pinfunction "VOUT_7") (pintype "output"))
    )
    (net (code "73") (name "Net-(U10-VOUT)") (class "Default")
      (node (ref "R30") (pin "1") (pinfunction "1_1") (pintype "passive"))
      (node (ref "U10") (pin "7") (pinfunction "VOUT_7") (pintype "output"))
    )
    (net (code "74") (name "Net-(U11-VOUT)") (class "Default")
      (node (ref "R31") (pin "1") (pinfunction "1_1") (pintype "passive"))
      (node (ref "U11") (pin "7") (pinfunction "VOUT_7") (pintype "output"))
    )
    (net (code "75") (name "Net-(U12-VOUT)") (class "Default")
      (node (ref "R32") (pin "1") (pinfunction "1_1") (pintype "passive"))
      (node (ref "U12") (pin "7") (pinfunction "VOUT_7") (pintype "output"))
    )
    (net (code "76") (name "Net-(U13-VOUT)") (class "Default")
      (node (ref "R37") (pin "1") (pinfunction "1_1") (pintype "passive"))
      (node (ref "U13") (pin "7") (pinfunction "VOUT_7") (pintype "output"))
    )
    (net (code "77") (name "Net-(U14-VOUT)") (class "Default")
      (node (ref "R38") (pin "1") (pinfunction "1_1") (pintype "passive"))
      (node (ref "U14") (pin "7") (pinfunction "VOUT_7") (pintype "output"))
    )
    (net (code "78") (name "Net-(U15-VOUT)") (class "Default")
      (node (ref "R39") (pin "1") (pinfunction "1_1") (pintype "passive"))
      (node (ref "U15") (pin "7") (pinfunction "VOUT_7") (pintype "output"))
    )
    (net (code "79") (name "Net-(U16-VOUT)") (class "Default")
      (node (ref "R40") (pin "1") (pinfunction "1_1") (pintype "passive"))
      (node (ref "U16") (pin "7") (pinfunction "VOUT_7") (pintype "output"))
    )
    (net (code "80") (name "Net-(U17-VOUT)") (class "Default")
      (node (ref "R45") (pin "1") (pinfunction "1_1") (pintype "passive"))
      (node (ref "U17") (pin "7") (pinfunction "VOUT_7") (pintype "output"))
    )
    (net (code "81") (name "Net-(U18-VOUT)") (class "Default")
      (node (ref "R46") (pin "1") (pinfunction "1_1") (pintype "passive"))
      (node (ref "U18") (pin "7") (pinfunction "VOUT_7") (pintype "output"))
    )
    (net (code "82") (name "Net-(U19-VOUT)") (class "Default")
      (node (ref "R47") (pin "1") (pinfunction "1_1") (pintype "passive"))
      (node (ref "U19") (pin "7") (pinfunction "VOUT_7") (pintype "output"))
    )
    (net (code "83") (name "Net-(U20-VOUT)") (class "Default")
      (node (ref "R48") (pin "1") (pinfunction "1_1") (pintype "passive"))
      (node (ref "U20") (pin "7") (pinfunction "VOUT_7") (pintype "output"))
    )
    (net (code "84") (name "unconnected-(J3-Pad1)") (class "Default")
      (node (ref "J3") (pin "1") (pinfunction "1_1") (pintype "passive+no_connect"))
    )
    (net (code "85") (name "unconnected-(J4-Pad10)") (class "Default")
      (node (ref "J4") (pin "10") (pinfunction "10_10") (pintype "passive+no_connect"))
    )
  )
)
